# Pneumatics_Board_Top.net
KiCad netlist of a schematic drawn in Altium Designer
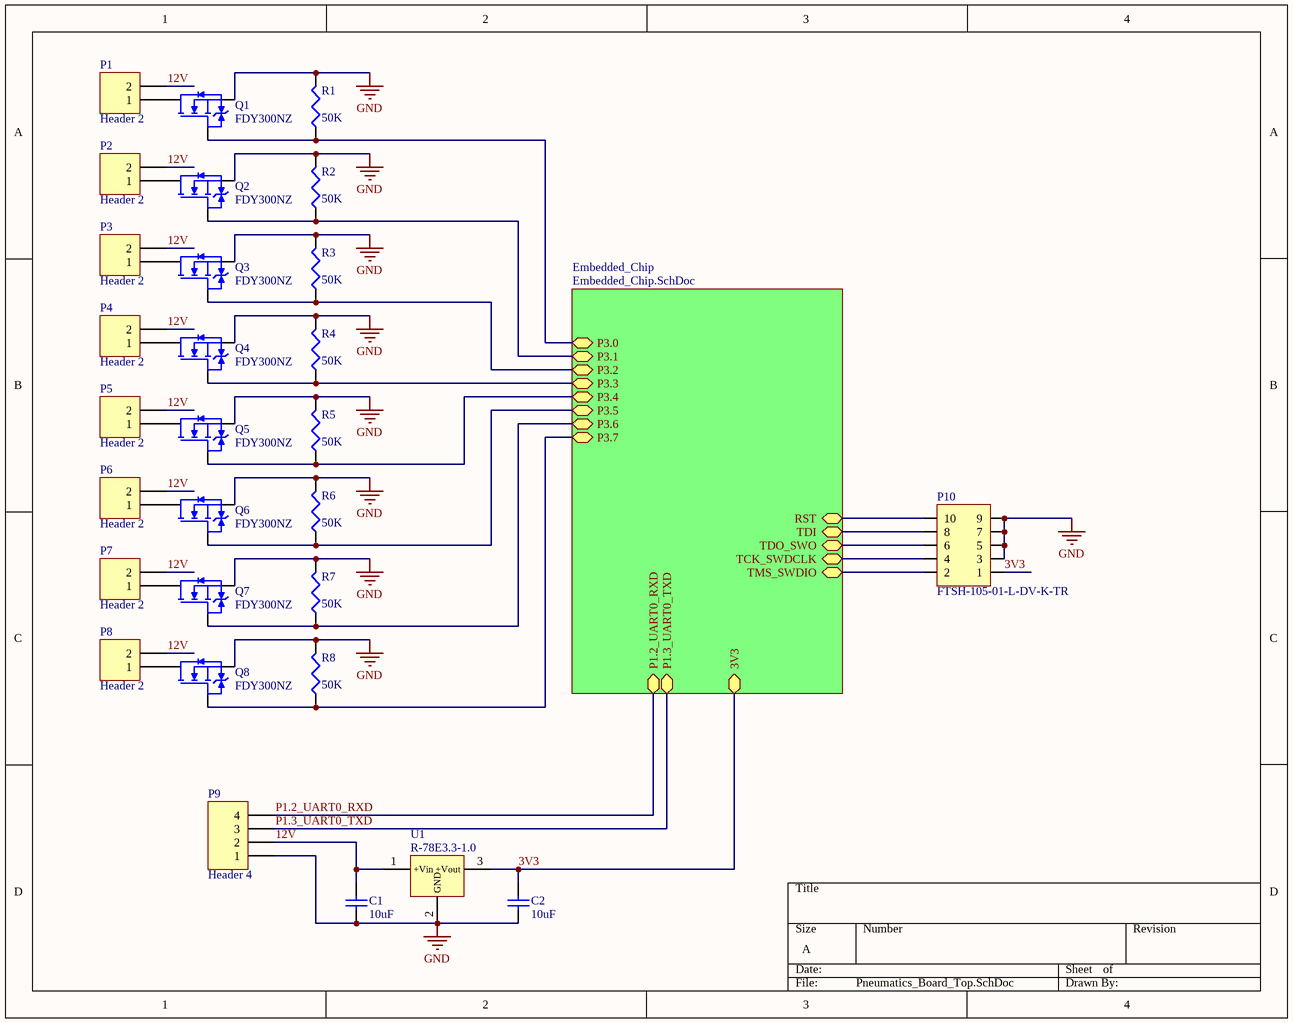
[diagram p0: Pneumatics_Board_Top.SchDoc]

(export (version "E")
  (design (tool "Eeschema 10.0.6"))
  (components
    (comp (ref "C1")
      (value "10uF")
      (footprint "C1206")
      (description "Capacitor (Semiconductor SIM Model)")
      (fields (field (name "Comment") "Cap Semi") (field (name "PUBLISHER") "Altium Limited"))
      (libsource (lib "Miscellaneous Devices") (part "Cap Semi"))
    )
    (comp (ref "C2")
      (value "10uF")
      (footprint "C1206")
      (description "Capacitor (Semiconductor SIM Model)")
      (fields (field (name "Comment") "Cap Semi") (field (name "PUBLISHER") "Altium Limited"))
      (libsource (lib "Miscellaneous Devices") (part "Cap Semi"))
    )
    (comp (ref "P1")
      (value "Header 2")
      (footprint "HDR1X2")
      (description "Header, 2-Pin")
      (fields (field (name "PUBLISHER") "Altium Limited"))
      (libsource (lib "Miscellaneous Connectors") (part "Header 2"))
    )
    (comp (ref "P2")
      (value "Header 2")
      (footprint "HDR1X2")
      (description "Header, 2-Pin")
      (fields (field (name "PUBLISHER") "Altium Limited"))
      (libsource (lib "Miscellaneous Connectors") (part "Header 2"))
    )
    (comp (ref "P3")
      (value "Header 2")
      (footprint "HDR1X2")
      (description "Header, 2-Pin")
      (fields (field (name "PUBLISHER") "Altium Limited"))
      (libsource (lib "Miscellaneous Connectors") (part "Header 2"))
    )
    (comp (ref "P4")
      (value "Header 2")
      (footprint "HDR1X2")
      (description "Header, 2-Pin")
      (fields (field (name "PUBLISHER") "Altium Limited"))
      (libsource (lib "Miscellaneous Connectors") (part "Header 2"))
    )
    (comp (ref "P5")
      (value "Header 2")
      (footprint "HDR1X2")
      (description "Header, 2-Pin")
      (fields (field (name "PUBLISHER") "Altium Limited"))
      (libsource (lib "Miscellaneous Connectors") (part "Header 2"))
    )
    (comp (ref "P6")
      (value "Header 2")
      (footprint "HDR1X2")
      (description "Header, 2-Pin")
      (fields (field (name "PUBLISHER") "Altium Limited"))
      (libsource (lib "Miscellaneous Connectors") (part "Header 2"))
    )
    (comp (ref "P7")
      (value "Header 2")
      (footprint "HDR1X2")
      (description "Header, 2-Pin")
      (fields (field (name "PUBLISHER") "Altium Limited"))
      (libsource (lib "Miscellaneous Connectors") (part "Header 2"))
    )
    (comp (ref "P8")
      (value "Header 2")
      (footprint "HDR1X2")
      (description "Header, 2-Pin")
      (fields (field (name "PUBLISHER") "Altium Limited"))
      (libsource (lib "Miscellaneous Connectors") (part "Header 2"))
    )
    (comp (ref "P9")
      (value "Header 4")
      (footprint "HDR1X4")
      (description "Header, 4-Pin")
      (fields (field (name "PUBLISHER") "Altium Limited"))
      (libsource (lib "Miscellaneous Connectors") (part "Header 4"))
    )
    (comp (ref "P10")
      (value "FTSH-105-01-L-DV-K-TR")
      (footprint "FTSH-105-01-L-DV-K-TR")
      (description "CONN HEADER 10POS DUAL .05\" SMD")
      (libsource (lib "Pneumatics_Board_Library") (part "JTAG Header"))
    )
    (comp (ref "Q1")
      (value "FDY300NZ")
      (footprint "FDY300NZ")
      (description "N-Channel 20V 600mA (Ta) 625mW (Ta) Surface Mount SC-89-3")
      (libsource (lib "Pneumatics_Board_Library") (part "FDY300NZ"))
    )
    (comp (ref "Q2")
      (value "FDY300NZ")
      (footprint "FDY300NZ")
      (description "N-Channel 20V 600mA (Ta) 625mW (Ta) Surface Mount SC-89-3")
      (libsource (lib "Pneumatics_Board_Library") (part "FDY300NZ"))
    )
    (comp (ref "Q3")
      (value "FDY300NZ")
      (footprint "FDY300NZ")
      (description "N-Channel 20V 600mA (Ta) 625mW (Ta) Surface Mount SC-89-3")
      (libsource (lib "Pneumatics_Board_Library") (part "FDY300NZ"))
    )
    (comp (ref "Q4")
      (value "FDY300NZ")
      (footprint "FDY300NZ")
      (description "N-Channel 20V 600mA (Ta) 625mW (Ta) Surface Mount SC-89-3")
      (libsource (lib "Pneumatics_Board_Library") (part "FDY300NZ"))
    )
    (comp (ref "Q5")
      (value "FDY300NZ")
      (footprint "FDY300NZ")
      (description "N-Channel 20V 600mA (Ta) 625mW (Ta) Surface Mount SC-89-3")
      (libsource (lib "Pneumatics_Board_Library") (part "FDY300NZ"))
    )
    (comp (ref "Q6")
      (value "FDY300NZ")
      (footprint "FDY300NZ")
      (description "N-Channel 20V 600mA (Ta) 625mW (Ta) Surface Mount SC-89-3")
      (libsource (lib "Pneumatics_Board_Library") (part "FDY300NZ"))
    )
    (comp (ref "Q7")
      (value "FDY300NZ")
      (footprint "FDY300NZ")
      (description "N-Channel 20V 600mA (Ta) 625mW (Ta) Surface Mount SC-89-3")
      (libsource (lib "Pneumatics_Board_Library") (part "FDY300NZ"))
    )
    (comp (ref "Q8")
      (value "FDY300NZ")
      (footprint "FDY300NZ")
      (description "N-Channel 20V 600mA (Ta) 625mW (Ta) Surface Mount SC-89-3")
      (libsource (lib "Pneumatics_Board_Library") (part "FDY300NZ"))
    )
    (comp (ref "R1")
      (value "50K")
      (footprint "J1-0603")
      (description "Resistor")
      (fields (field (name "Comment") "Res3") (field (name "PUBLISHER") "Altium Limited"))
      (libsource (lib "Miscellaneous Devices") (part "Res3"))
    )
    (comp (ref "R2")
      (value "50K")
      (footprint "J1-0603")
      (description "Resistor")
      (fields (field (name "Comment") "Res3") (field (name "PUBLISHER") "Altium Limited"))
      (libsource (lib "Miscellaneous Devices") (part "Res3"))
    )
    (comp (ref "R3")
      (value "50K")
      (footprint "J1-0603")
      (description "Resistor")
      (fields (field (name "Comment") "Res3") (field (name "PUBLISHER") "Altium Limited"))
      (libsource (lib "Miscellaneous Devices") (part "Res3"))
    )
    (comp (ref "R4")
      (value "50K")
      (footprint "J1-0603")
      (description "Resistor")
      (fields (field (name "Comment") "Res3") (field (name "PUBLISHER") "Altium Limited"))
      (libsource (lib "Miscellaneous Devices") (part "Res3"))
    )
    (comp (ref "R5")
      (value "50K")
      (footprint "J1-0603")
      (description "Resistor")
      (fields (field (name "Comment") "Res3") (field (name "PUBLISHER") "Altium Limited"))
      (libsource (lib "Miscellaneous Devices") (part "Res3"))
    )
    (comp (ref "R6")
      (value "50K")
      (footprint "J1-0603")
      (description "Resistor")
      (fields (field (name "Comment") "Res3") (field (name "PUBLISHER") "Altium Limited"))
      (libsource (lib "Miscellaneous Devices") (part "Res3"))
    )
    (comp (ref "R7")
      (value "50K")
      (footprint "J1-0603")
      (description "Resistor")
      (fields (field (name "Comment") "Res3") (field (name "PUBLISHER") "Altium Limited"))
      (libsource (lib "Miscellaneous Devices") (part "Res3"))
    )
    (comp (ref "R8")
      (value "50K")
      (footprint "J1-0603")
      (description "Resistor")
      (fields (field (name "Comment") "Res3") (field (name "PUBLISHER") "Altium Limited"))
      (libsource (lib "Miscellaneous Devices") (part "Res3"))
    )
    (comp (ref "U1")
      (value "R-78E3.3-1.0")
      (footprint "R-78Exx-1.0")
      (description "1A DC/DC Voltage Converter")
      (libsource (lib "Pneumatics_Board_Library") (part "R-78Exx-1.0"))
    )
  )
  (nets
    (net (code "1") (name "/3V3") (class "Default")
      (node (ref "C2") (pin "2") (pinfunction "2_2") (pintype "passive"))
      (node (ref "P10") (pin "1") (pinfunction "1_1") (pintype "passive"))
      (node (ref "U1") (pin "3") (pinfunction "+Vout_3") (pintype "passive"))
    )
    (net (code "2") (name "/12V") (class "Default")
      (node (ref "C1") (pin "2") (pinfunction "2_2") (pintype "passive"))
      (node (ref "P1") (pin "2") (pinfunction "2_2") (pintype "passive"))
      (node (ref "P2") (pin "2") (pinfunction "2_2") (pintype "passive"))
      (node (ref "P3") (pin "2") (pinfunction "2_2") (pintype "passive"))
      (node (ref "P4") (pin "2") (pinfunction "2_2") (pintype "passive"))
      (node (ref "P5") (pin "2") (pinfunction "2_2") (pintype "passive"))
      (node (ref "P6") (pin "2") (pinfunction "2_2") (pintype "passive"))
      (node (ref "P7") (pin "2") (pinfunction "2_2") (pintype "passive"))
      (node (ref "P8") (pin "2") (pinfunction "2_2") (pintype "passive"))
      (node (ref "P9") (pin "2") (pinfunction "2_2") (pintype "passive"))
      (node (ref "U1") (pin "1") (pinfunction "+Vin_1") (pintype "passive"))
    )
    (net (code "3") (name "/P1.2_UART0_RXD") (class "Default")
      (node (ref "P9") (pin "4") (pinfunction "4_4") (pintype "passive"))
    )
    (net (code "4") (name "/P1.3_UART0_TXD") (class "Default")
      (node (ref "P9") (pin "3") (pinfunction "3_3") (pintype "passive"))
    )
    (net (code "5") (name "/P3.0") (class "Default")
      (node (ref "Q1") (pin "1") (pinfunction "Gate_1") (pintype "passive"))
      (node (ref "R1") (pin "1") (pinfunction "1_1") (pintype "passive"))
    )
    (net (code "6") (name "/P3.1") (class "Default")
      (node (ref "Q2") (pin "1") (pinfunction "Gate_1") (pintype "passive"))
      (node (ref "R2") (pin "1") (pinfunction "1_1") (pintype "passive"))
    )
    (net (code "7") (name "/P3.2") (class "Default")
      (node (ref "Q3") (pin "1") (pinfunction "Gate_1") (pintype "passive"))
      (node (ref "R3") (pin "1") (pinfunction "1_1") (pintype "passive"))
    )
    (net (code "8") (name "/P3.3") (class "Default")
      (node (ref "Q4") (pin "1") (pinfunction "Gate_1") (pintype "passive"))
      (node (ref "R4") (pin "1") (pinfunction "1_1") (pintype "passive"))
    )
    (net (code "9") (name "/P3.4") (class "Default")
      (node (ref "Q5") (pin "1") (pinfunction "Gate_1") (pintype "passive"))
      (node (ref "R5") (pin "1") (pinfunction "1_1") (pintype "passive"))
    )
    (net (code "10") (name "/P3.5") (class "Default")
      (node (ref "Q6") (pin "1") (pinfunction "Gate_1") (pintype "passive"))
      (node (ref "R6") (pin "1") (pinfunction "1_1") (pintype "passive"))
    )
    (net (code "11") (name "/P3.6") (class "Default")
      (node (ref "Q7") (pin "1") (pinfunction "Gate_1") (pintype "passive"))
      (node (ref "R7") (pin "1") (pinfunction "1_1") (pintype "passive"))
    )
    (net (code "12") (name "/P3.7") (class "Default")
      (node (ref "Q8") (pin "1") (pinfunction "Gate_1") (pintype "passive"))
      (node (ref "R8") (pin "1") (pinfunction "1_1") (pintype "passive"))
    )
    (net (code "13") (name "/RST") (class "Default")
      (node (ref "P10") (pin "10") (pinfunction "10_10") (pintype "passive"))
    )
    (net (code "14") (name "/TCK_SWDCLK") (class "Default")
      (node (ref "P10") (pin "4") (pinfunction "4_4") (pintype "passive"))
    )
    (net (code "15") (name "/TDI") (class "Default")
      (node (ref "P10") (pin "8") (pinfunction "8_8") (pintype "passive"))
    )
    (net (code "16") (name "/TDO_SWO") (class "Default")
      (node (ref "P10") (pin "6") (pinfunction "6_6") (pintype "passive"))
    )
    (net (code "17") (name "/TMS_SWDIO") (class "Default")
      (node (ref "P10") (pin "2") (pinfunction "2_2") (pintype "passive"))
    )
    (net (code "18") (name "GND") (class "Default")
      (node (ref "C1") (pin "1") (pinfunction "1_1") (pintype "passive"))
      (node (ref "C2") (pin "1") (pinfunction "1_1") (pintype "passive"))
      (node (ref "P10") (pin "3") (pinfunction "3_3") (pintype "passive"))
      (node (ref "P10") (pin "5") (pinfunction "5_5") (pintype "passive"))
      (node (ref "P10") (pin "7") (pinfunction "7_7") (pintype "passive"))
      (node (ref "P10") (pin "9") (pinfunction "9_9") (pintype "passive"))
      (node (ref "P9") (pin "1") (pinfunction "1_1") (pintype "passive"))
      (node (ref "Q1") (pin "2") (pinfunction "Source_2") (pintype "passive"))
      (node (ref "Q2") (pin "2") (pinfunction "Source_2") (pintype "passive"))
      (node (ref "Q3") (pin "2") (pinfunction "Source_2") (pintype "passive"))
      (node (ref "Q4") (pin "2") (pinfunction "Source_2") (pintype "passive"))
      (node (ref "Q5") (pin "2") (pinfunction "Source_2") (pintype "passive"))
      (node (ref "Q6") (pin "2") (pinfunction "Source_2") (pintype "passive"))
      (node (ref "Q7") (pin "2") (pinfunction "Source_2") (pintype "passive"))
      (node (ref "Q8") (pin "2") (pinfunction "Source_2") (pintype "passive"))
      (node (ref "R1") (pin "2") (pinfunction "2_2") (pintype "passive"))
      (node (ref "R2") (pin "2") (pinfunction "2_2") (pintype "passive"))
      (node (ref "R3") (pin "2") (pinfunction "2_2") (pintype "passive"))
      (node (ref "R4") (pin "2") (pinfunction "2_2") (pintype "passive"))
      (node (ref "R5") (pin "2") (pinfunction "2_2") (pintype "passive"))
      (node (ref "R6") (pin "2") (pinfunction "2_2") (pintype "passive"))
      (node (ref "R7") (pin "2") (pinfunction "2_2") (pintype "passive"))
      (node (ref "R8") (pin "2") (pinfunction "2_2") (pintype "passive"))
      (node (ref "U1") (pin "2") (pinfunction "GND_2") (pintype "passive"))
    )
    (net (code "19") (name "Net-(Q1-Drain)") (class "Default")
      (node (ref "P1") (pin "1") (pinfunction "1_1") (pintype "passive"))
      (node (ref "Q1") (pin "3") (pinfunction "Drain_3") (pintype "passive"))
    )
    (net (code "20") (name "Net-(Q2-Drain)") (class "Default")
      (node (ref "P2") (pin "1") (pinfunction "1_1") (pintype "passive"))
      (node (ref "Q2") (pin "3") (pinfunction "Drain_3") (pintype "passive"))
    )
    (net (code "21") (name "Net-(Q3-Drain)") (class "Default")
      (node (ref "P3") (pin "1") (pinfunction "1_1") (pintype "passive"))
      (node (ref "Q3") (pin "3") (pinfunction "Drain_3") (pintype "passive"))
    )
    (net (code "22") (name "Net-(Q4-Drain)") (class "Default")
      (node (ref "P4") (pin "1") (pinfunction "1_1") (pintype "passive"))
      (node (ref "Q4") (pin "3") (pinfunction "Drain_3") (pintype "passive"))
    )
    (net (code "23") (name "Net-(Q5-Drain)") (class "Default")
      (node (ref "P5") (pin "1") (pinfunction "1_1") (pintype "passive"))
      (node (ref "Q5") (pin "3") (pinfunction "Drain_3") (pintype "passive"))
    )
    (net (code "24") (name "Net-(Q6-Drain)") (class "Default")
      (node (ref "P6") (pin "1") (pinfunction "1_1") (pintype "passive"))
      (node (ref "Q6") (pin "3") (pinfunction "Drain_3") (pintype "passive"))
    )
    (net (code "25") (name "Net-(Q7-Drain)") (class "Default")
      (node (ref "P7") (pin "1") (pinfunction "1_1") (pintype "passive"))
      (node (ref "Q7") (pin "3") (pinfunction "Drain_3") (pintype "passive"))
    )
    (net (code "26") (name "Net-(Q8-Drain)") (class "Default")
      (node (ref "P8") (pin "1") (pinfunction "1_1") (pintype "passive"))
      (node (ref "Q8") (pin "3") (pinfunction "Drain_3") (pintype "passive"))
    )
  )
)
